# power.net
KiCad netlist of a schematic drawn in Altium Designer
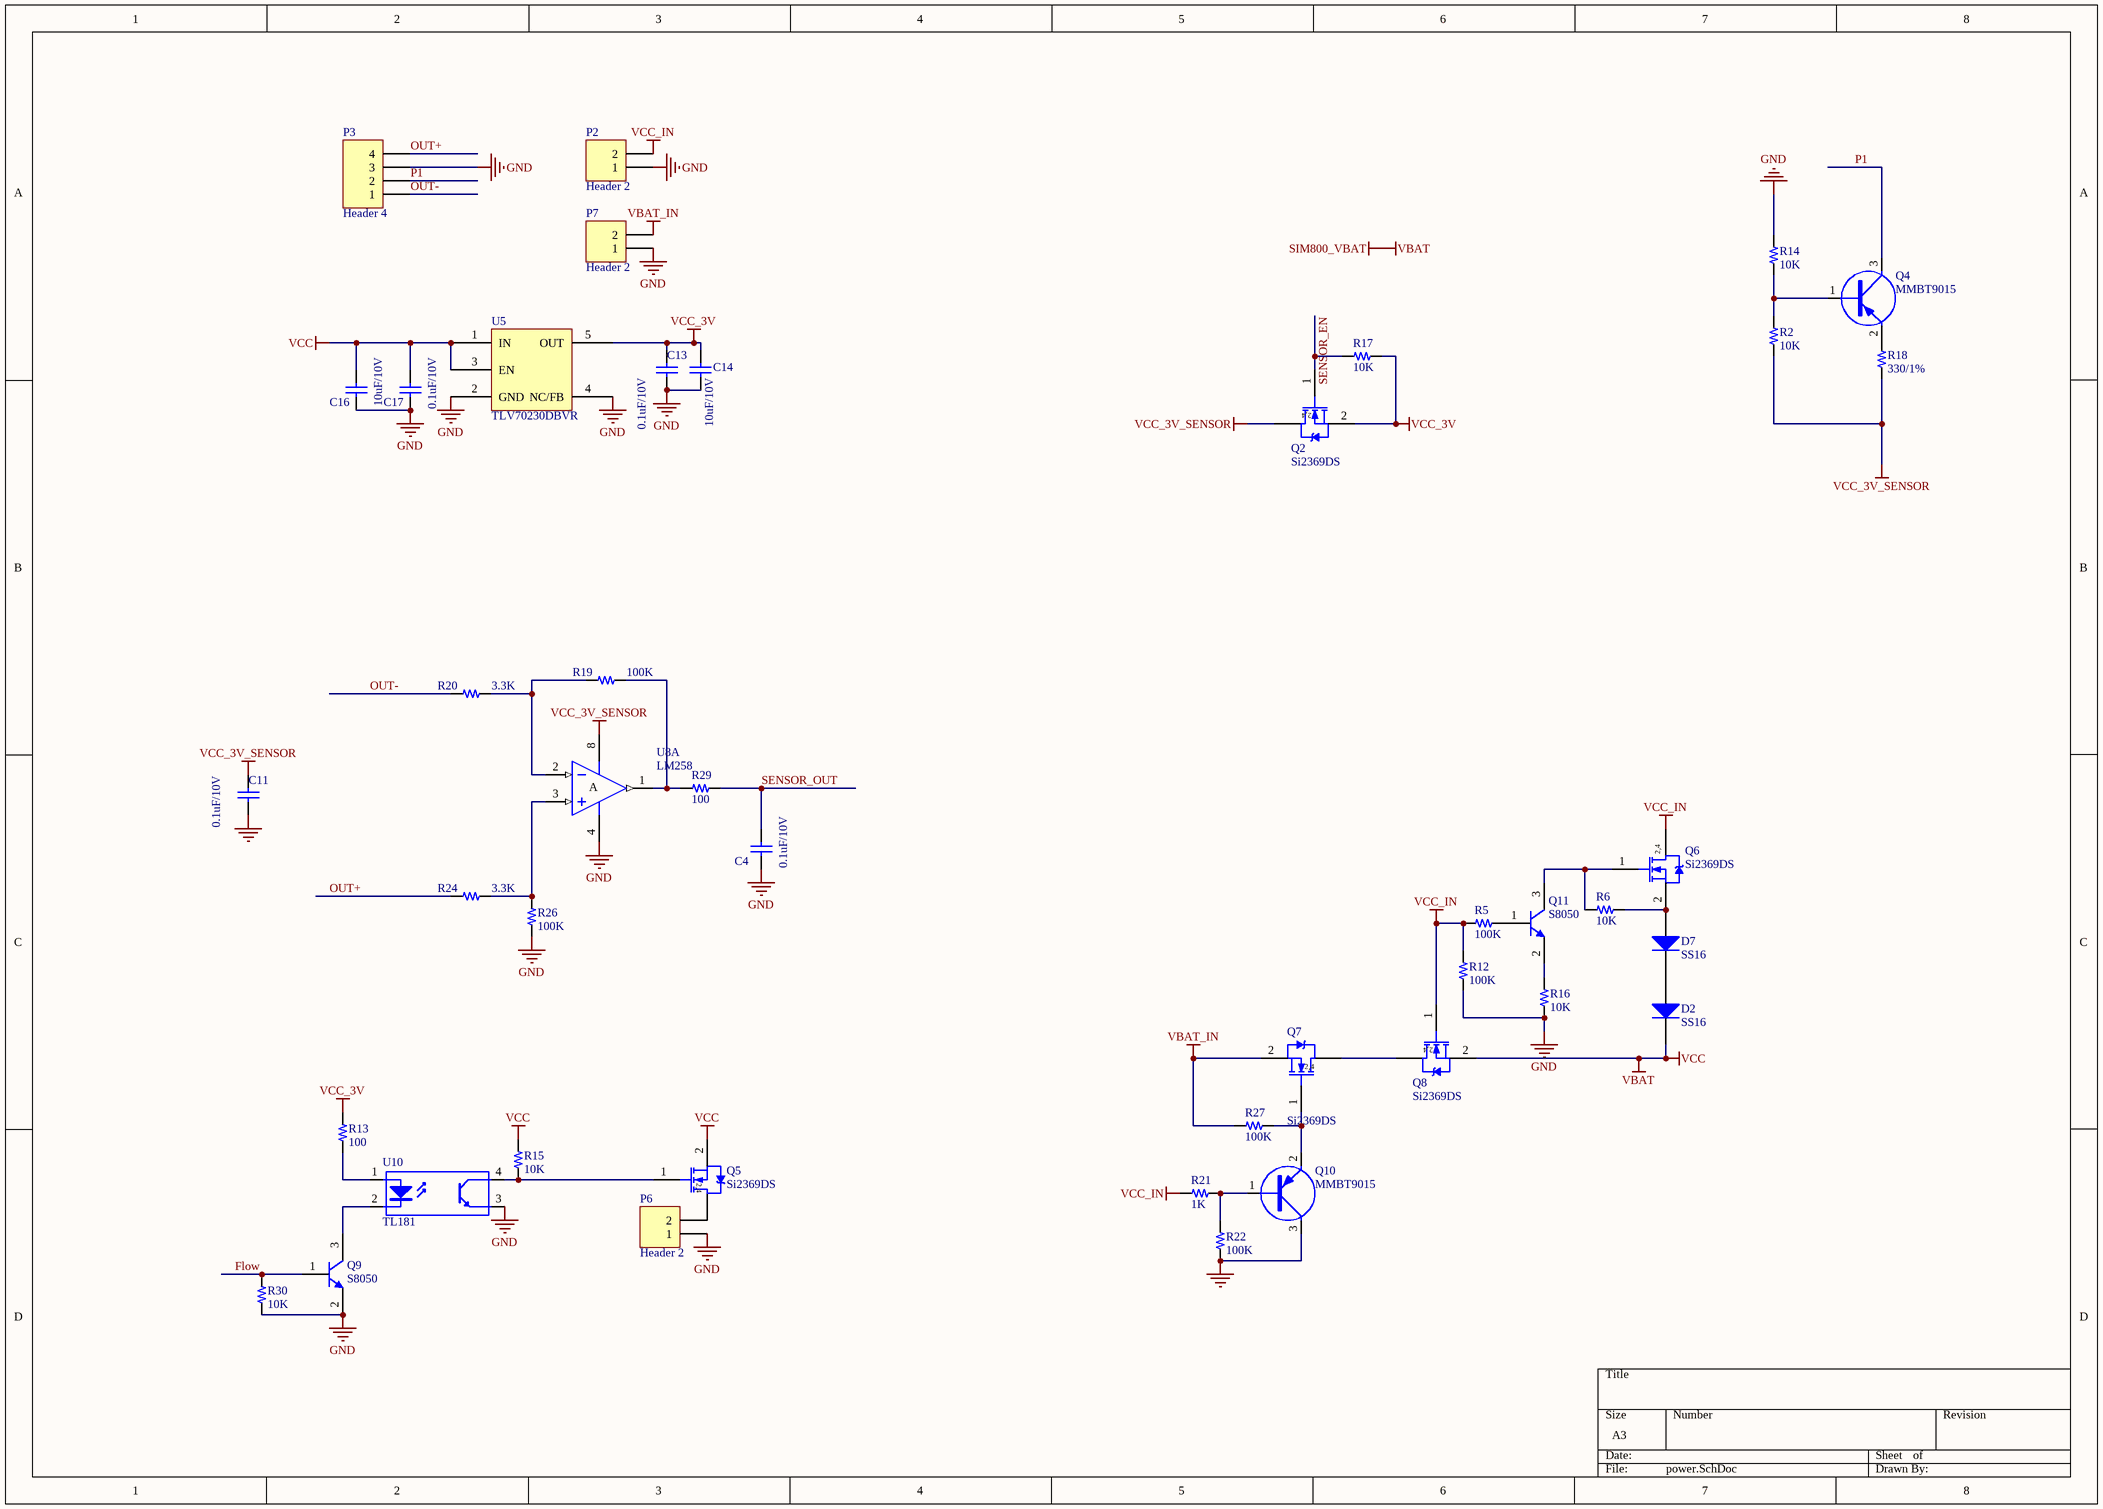
[diagram p0: power.SchDoc]

(export (version "E")
  (design (tool "Eeschema 10.0.6"))
  (components
    (comp (ref "C4")
      (value "0.1uF/10V")
      (footprint "0603C")
      (description "Capacitor")
      (fields (field (name "PUBLISHER") "Altium Limited"))
      (libsource (lib "Miscellaneous Devices") (part "Cap"))
    )
    (comp (ref "C11")
      (value "0.1uF/10V")
      (footprint "0603C")
      (description "Capacitor")
      (fields (field (name "PUBLISHER") "Altium Limited"))
      (libsource (lib "Miscellaneous Devices") (part "Cap"))
    )
    (comp (ref "C13")
      (value "0.1uF/10V")
      (footprint "0603C")
      (description "Capacitor")
      (fields (field (name "PUBLISHER") "Altium Limited"))
      (libsource (lib "Miscellaneous Devices") (part "Cap"))
    )
    (comp (ref "C14")
      (value "10uF/10V")
      (footprint "0603C")
      (description "Capacitor")
      (fields (field (name "PUBLISHER") "Altium Limited"))
      (libsource (lib "Miscellaneous Devices") (part "Cap"))
    )
    (comp (ref "C16")
      (value "10uF/10V")
      (footprint "0603C")
      (description "Capacitor")
      (fields (field (name "PUBLISHER") "Altium Limited"))
      (libsource (lib "Miscellaneous Devices") (part "Cap"))
    )
    (comp (ref "C17")
      (value "0.1uF/10V")
      (footprint "0603C")
      (description "Capacitor")
      (fields (field (name "PUBLISHER") "Altium Limited"))
      (libsource (lib "Miscellaneous Devices") (part "Cap"))
    )
    (comp (ref "D2")
      (value "SS16")
      (footprint "SMA")
      (description "High Conductance Fast Diode")
      (fields (field (name "PUBLISHER") "Altium Limited"))
      (libsource (lib "Miscellaneous Devices") (part "Diode 1N4148"))
    )
    (comp (ref "D7")
      (value "SS16")
      (footprint "SMA")
      (description "High Conductance Fast Diode")
      (fields (field (name "PUBLISHER") "Altium Limited"))
      (libsource (lib "Miscellaneous Devices") (part "Diode 1N4148"))
    )
    (comp (ref "P2")
      (value "Header 2")
      (footprint "2X2.54MM")
      (description "Header, 2-Pin")
      (fields (field (name "PUBLISHER") "Altium Limited"))
      (libsource (lib "Miscellaneous Connectors") (part "Header 2"))
    )
    (comp (ref "P3")
      (value "Header 4")
      (footprint "HDR1X4")
      (description "Header, 4-Pin")
      (fields (field (name "PUBLISHER") "Altium Limited"))
      (libsource (lib "Miscellaneous Connectors") (part "Header 4"))
    )
    (comp (ref "P6")
      (value "Header 2")
      (footprint "HDR1X2")
      (description "Header, 2-Pin")
      (fields (field (name "PUBLISHER") "Altium Limited"))
      (libsource (lib "Miscellaneous Connectors") (part "Header 2"))
    )
    (comp (ref "P7")
      (value "Header 2")
      (footprint "2X2.54MM")
      (description "Header, 2-Pin")
      (fields (field (name "PUBLISHER") "Altium Limited"))
      (libsource (lib "Miscellaneous Connectors") (part "Header 2"))
    )
    (comp (ref "Q2")
      (value "Si2369DS")
      (footprint "SOT23-3")
      (description "BUK92150-55A")
      (fields (field (name "PUBLISHER") "Altium Limited"))
      (libsource (lib "Schlib1") (part "BUK92150-55A"))
    )
    (comp (ref "Q4") (value "MMBT9015") (footprint "SOT23-3") (libsource (lib "Schlib1") (part "PNP")))
    (comp (ref "Q5")
      (value "Si2369DS")
      (footprint "SOT23-3")
      (description "BUK92150-55A")
      (fields (field (name "PUBLISHER") "Altium Limited"))
      (libsource (lib "") (part "BUK92150-55A_1"))
    )
    (comp (ref "Q6")
      (value "Si2369DS")
      (footprint "SOT23-3")
      (description "BUK92150-55A")
      (fields (field (name "PUBLISHER") "Altium Limited"))
      (libsource (lib "") (part "BUK92150-55A_1"))
    )
    (comp (ref "Q7")
      (value "Si2369DS")
      (footprint "SOT23-3")
      (description "BUK92150-55A")
      (fields (field (name "PUBLISHER") "Altium Limited"))
      (libsource (lib "Schlib1") (part "BUK92150-55A"))
    )
    (comp (ref "Q8")
      (value "Si2369DS")
      (footprint "SOT23-3")
      (description "BUK92150-55A")
      (fields (field (name "PUBLISHER") "Altium Limited"))
      (libsource (lib "Schlib1") (part "BUK92150-55A"))
    )
    (comp (ref "Q9") (value "S8050") (footprint "SOT23-3") (libsource (lib "Schlib1") (part "NPN")))
    (comp (ref "Q10") (value "MMBT9015") (footprint "SOT23-3") (libsource (lib "Schlib1") (part "PNP")))
    (comp (ref "Q11") (value "S8050") (footprint "SOT23-3") (libsource (lib "Schlib1") (part "NPN")))
    (comp (ref "R2") (value "10K") (footprint "0603R") (description "R") (libsource (lib "JRJ_1") (part "R")))
    (comp (ref "R5")
      (value "100K")
      (footprint "0603R")
      (description "R")
      (libsource (lib "JRJ_1") (part "R"))
    )
    (comp (ref "R6") (value "10K") (footprint "0603R") (description "R") (libsource (lib "JRJ_1") (part "R")))
    (comp (ref "R12")
      (value "100K")
      (footprint "0603R")
      (description "R")
      (libsource (lib "JRJ_1") (part "R"))
    )
    (comp (ref "R13")
      (value "100")
      (footprint "0603R")
      (description "R")
      (libsource (lib "JRJ_1") (part "R"))
    )
    (comp (ref "R14")
      (value "10K")
      (footprint "0603R")
      (description "R")
      (libsource (lib "JRJ_1") (part "R"))
    )
    (comp (ref "R15")
      (value "10K")
      (footprint "0603R")
      (description "R")
      (libsource (lib "JRJ_1") (part "R"))
    )
    (comp (ref "R16")
      (value "10K")
      (footprint "0603R")
      (description "R")
      (libsource (lib "JRJ_1") (part "R"))
    )
    (comp (ref "R17")
      (value "10K")
      (footprint "0603R")
      (description "R")
      (libsource (lib "JRJ_1") (part "R"))
    )
    (comp (ref "R18")
      (value "330/1%")
      (footprint "0603R")
      (description "R")
      (libsource (lib "JRJ_1") (part "R"))
    )
    (comp (ref "R19")
      (value "100K")
      (footprint "0603R")
      (description "R")
      (libsource (lib "JRJ_1") (part "R"))
    )
    (comp (ref "R20")
      (value "3.3K")
      (footprint "0603R")
      (description "R")
      (libsource (lib "JRJ_1") (part "R"))
    )
    (comp (ref "R21") (value "1K") (footprint "0603R") (description "R") (libsource (lib "JRJ_1") (part "R")))
    (comp (ref "R22")
      (value "100K")
      (footprint "0603R")
      (description "R")
      (libsource (lib "JRJ_1") (part "R"))
    )
    (comp (ref "R24")
      (value "3.3K")
      (footprint "0603R")
      (description "R")
      (libsource (lib "JRJ_1") (part "R"))
    )
    (comp (ref "R26")
      (value "100K")
      (footprint "0603R")
      (description "R")
      (libsource (lib "JRJ_1") (part "R"))
    )
    (comp (ref "R27")
      (value "100K")
      (footprint "0603R")
      (description "R")
      (libsource (lib "JRJ_1") (part "R"))
    )
    (comp (ref "R29")
      (value "100")
      (footprint "0603R")
      (description "R")
      (libsource (lib "JRJ_1") (part "R"))
    )
    (comp (ref "R30")
      (value "10K")
      (footprint "0603R")
      (description "R")
      (libsource (lib "JRJ_1") (part "R"))
    )
    (comp (ref "U5")
      (value "TLV70230DBVR")
      (footprint "SOT23-5(DBV)")
      (libsource (lib "Schlib_20110825") (part "TLV70230DBVR"))
    )
    (comp (ref "U8") (value "LM258") (footprint "so-8") (libsource (lib "Schlib_20110825") (part "LM258")))
    (comp (ref "U10")
      (value "TL181")
      (footprint "DIP-4")
      (description "4-Pin Phototransistor Optocoupler")
      (fields (field (name "PUBLISHER") "Altium Limited"))
      (libsource (lib "Miscellaneous Devices") (part "Optoisolator1"))
    )
  )
  (nets
    (net (code "1") (name "/Flow") (class "Default")
      (node (ref "Q9") (pin "1") (pinfunction "B_1") (pintype "passive"))
      (node (ref "R30") (pin "2") (pintype "passive"))
    )
    (net (code "2") (name "/OUT+") (class "Default")
      (node (ref "P3") (pin "4") (pinfunction "4_4") (pintype "passive"))
      (node (ref "R24") (pin "1") (pintype "passive"))
    )
    (net (code "3") (name "/OUT-") (class "Default")
      (node (ref "P3") (pin "1") (pinfunction "1_1") (pintype "passive"))
      (node (ref "R20") (pin "1") (pintype "passive"))
    )
    (net (code "4") (name "/P1") (class "Default")
      (node (ref "P3") (pin "2") (pinfunction "2_2") (pintype "passive"))
      (node (ref "Q4") (pin "3") (pinfunction "C_3") (pintype "passive"))
    )
    (net (code "5") (name "/SENSOR_EN") (class "Default")
      (node (ref "Q2") (pin "1") (pinfunction "G_1") (pintype "passive"))
      (node (ref "R17") (pin "2") (pintype "passive"))
    )
    (net (code "6") (name "/SENSOR_OUT") (class "Default")
      (node (ref "C4") (pin "1") (pinfunction "1_1") (pintype "passive"))
      (node (ref "R29") (pin "2") (pintype "passive"))
    )
    (net (code "7") (name "GND") (class "Default")
      (node (ref "C11") (pin "2") (pinfunction "2_2") (pintype "passive"))
      (node (ref "C13") (pin "2") (pinfunction "2_2") (pintype "passive"))
      (node (ref "C14") (pin "1") (pinfunction "1_1") (pintype "passive"))
      (node (ref "C16") (pin "1") (pinfunction "1_1") (pintype "passive"))
      (node (ref "C17") (pin "2") (pinfunction "2_2") (pintype "passive"))
      (node (ref "C4") (pin "2") (pinfunction "2_2") (pintype "passive"))
      (node (ref "P2") (pin "1") (pinfunction "1_1") (pintype "passive"))
      (node (ref "P3") (pin "3") (pinfunction "3_3") (pintype "passive"))
      (node (ref "P6") (pin "1") (pinfunction "1_1") (pintype "passive"))
      (node (ref "P7") (pin "1") (pinfunction "1_1") (pintype "passive"))
      (node (ref "Q10") (pin "3") (pinfunction "C_3") (pintype "passive"))
      (node (ref "Q9") (pin "2") (pinfunction "E_2") (pintype "passive"))
      (node (ref "R12") (pin "2") (pintype "passive"))
      (node (ref "R14") (pin "2") (pintype "passive"))
      (node (ref "R16") (pin "1") (pintype "passive"))
      (node (ref "R22") (pin "1") (pintype "passive"))
      (node (ref "R26") (pin "1") (pintype "passive"))
      (node (ref "R30") (pin "1") (pintype "passive"))
      (node (ref "U10") (pin "3") (pinfunction "E_3") (pintype "passive"))
      (node (ref "U5") (pin "2") (pinfunction "GND_2") (pintype "passive"))
      (node (ref "U5") (pin "4") (pinfunction "NC/FB_4") (pintype "passive"))
      (node (ref "U8") (pin "4") (pinfunction "V-_4") (pintype "power_in"))
    )
    (net (code "8") (name "Net-(D2-A)") (class "Default")
      (node (ref "D2") (pin "1") (pinfunction "A_1") (pintype "passive"))
      (node (ref "D7") (pin "2") (pinfunction "K_2") (pintype "passive"))
    )
    (net (code "9") (name "Net-(D7-A)") (class "Default")
      (node (ref "D7") (pin "1") (pinfunction "A_1") (pintype "passive"))
      (node (ref "Q6") (pin "2") (pinfunction "S_2") (pintype "passive"))
      (node (ref "R6") (pin "1") (pintype "passive"))
    )
    (net (code "10") (name "Net-(Q4-B)") (class "Default")
      (node (ref "Q4") (pin "1") (pinfunction "B_1") (pintype "passive"))
      (node (ref "R14") (pin "1") (pintype "passive"))
      (node (ref "R2") (pin "2") (pintype "passive"))
    )
    (net (code "11") (name "Net-(Q4-E)") (class "Default")
      (node (ref "Q4") (pin "2") (pinfunction "E_2") (pintype "passive"))
      (node (ref "R18") (pin "2") (pintype "passive"))
    )
    (net (code "12") (name "Net-(Q5-D)") (class "Default")
      (node (ref "P6") (pin "2") (pinfunction "2_2") (pintype "passive"))
      (node (ref "Q5") (pin "3") (pinfunction "D_3") (pintype "passive"))
    )
    (net (code "13") (name "Net-(Q5-G)") (class "Default")
      (node (ref "Q5") (pin "1") (pinfunction "G_1") (pintype "passive"))
      (node (ref "R15") (pin "1") (pintype "passive"))
      (node (ref "U10") (pin "4") (pinfunction "C_4") (pintype "passive"))
    )
    (net (code "14") (name "Net-(Q7-D)") (class "Default")
      (node (ref "Q7") (pin "3") (pinfunction "D_3") (pintype "passive"))
      (node (ref "Q8") (pin "3") (pinfunction "D_3") (pintype "passive"))
    )
    (net (code "15") (name "Net-(Q9-C)") (class "Default")
      (node (ref "Q9") (pin "3") (pinfunction "C_3") (pintype "passive"))
      (node (ref "U10") (pin "2") (pinfunction "K_2") (pintype "passive"))
    )
    (net (code "16") (name "Net-(Q10-B)") (class "Default")
      (node (ref "Q10") (pin "1") (pinfunction "B_1") (pintype "passive"))
      (node (ref "R21") (pin "2") (pintype "passive"))
      (node (ref "R22") (pin "2") (pintype "passive"))
    )
    (net (code "17") (name "Net-(Q10-E)") (class "Default")
      (node (ref "Q10") (pin "2") (pinfunction "E_2") (pintype "passive"))
      (node (ref "Q7") (pin "1") (pinfunction "G_1") (pintype "passive"))
      (node (ref "R27") (pin "2") (pintype "passive"))
    )
    (net (code "18") (name "Net-(Q11-B)") (class "Default")
      (node (ref "Q11") (pin "1") (pinfunction "B_1") (pintype "passive"))
      (node (ref "R5") (pin "2") (pintype "passive"))
    )
    (net (code "19") (name "Net-(Q11-C)") (class "Default")
      (node (ref "Q11") (pin "3") (pinfunction "C_3") (pintype "passive"))
      (node (ref "Q6") (pin "1") (pinfunction "G_1") (pintype "passive"))
      (node (ref "R6") (pin "2") (pintype "passive"))
    )
    (net (code "20") (name "Net-(Q11-E)") (class "Default")
      (node (ref "Q11") (pin "2") (pinfunction "E_2") (pintype "passive"))
      (node (ref "R16") (pin "2") (pintype "passive"))
    )
    (net (code "21") (name "Net-(U8A-IN+)") (class "Default")
      (node (ref "R24") (pin "2") (pintype "passive"))
      (node (ref "R26") (pin "2") (pintype "passive"))
      (node (ref "U8") (pin "3") (pinfunction "IN+_3") (pintype "input"))
    )
    (net (code "22") (name "Net-(U8A-IN-)") (class "Default")
      (node (ref "R19") (pin "1") (pintype "passive"))
      (node (ref "R20") (pin "2") (pintype "passive"))
      (node (ref "U8") (pin "2") (pinfunction "IN-_2") (pintype "input"))
    )
    (net (code "23") (name "Net-(U8A-OUT)") (class "Default")
      (node (ref "R19") (pin "2") (pintype "passive"))
      (node (ref "R29") (pin "1") (pintype "passive"))
      (node (ref "U8") (pin "1") (pinfunction "OUT_1") (pintype "output"))
    )
    (net (code "24") (name "Net-(U10-A)") (class "Default")
      (node (ref "R13") (pin "1") (pintype "passive"))
      (node (ref "U10") (pin "1") (pinfunction "A_1") (pintype "passive"))
    )
    (net (code "25") (name "SIM800_VBAT") (class "Default")
      (node (ref "C16") (pin "2") (pinfunction "2_2") (pintype "passive"))
      (node (ref "C17") (pin "1") (pinfunction "1_1") (pintype "passive"))
      (node (ref "D2") (pin "2") (pinfunction "K_2") (pintype "passive"))
      (node (ref "Q5") (pin "2") (pinfunction "S_2") (pintype "passive"))
      (node (ref "Q8") (pin "2") (pinfunction "S_2") (pintype "passive"))
      (node (ref "R15") (pin "2") (pintype "passive"))
      (node (ref "U5") (pin "1") (pinfunction "IN_1") (pintype "passive"))
      (node (ref "U5") (pin "3") (pinfunction "EN_3") (pintype "passive"))
    )
    (net (code "26") (name "VBAT_IN") (class "Default")
      (node (ref "P7") (pin "2") (pinfunction "2_2") (pintype "passive"))
      (node (ref "Q7") (pin "2") (pinfunction "S_2") (pintype "passive"))
      (node (ref "R27") (pin "1") (pintype "passive"))
    )
    (net (code "27") (name "VCC_3V") (class "Default")
      (node (ref "C13") (pin "1") (pinfunction "1_1") (pintype "passive"))
      (node (ref "C14") (pin "2") (pinfunction "2_2") (pintype "passive"))
      (node (ref "Q2") (pin "2") (pinfunction "S_2") (pintype "passive"))
      (node (ref "R13") (pin "2") (pintype "passive"))
      (node (ref "R17") (pin "1") (pintype "passive"))
      (node (ref "U5") (pin "5") (pinfunction "OUT_5") (pintype "passive"))
    )
    (net (code "28") (name "VCC_3V_SENSOR") (class "Default")
      (node (ref "C11") (pin "1") (pinfunction "1_1") (pintype "passive"))
      (node (ref "Q2") (pin "3") (pinfunction "D_3") (pintype "passive"))
      (node (ref "R18") (pin "1") (pintype "passive"))
      (node (ref "R2") (pin "1") (pintype "passive"))
      (node (ref "U8") (pin "8") (pinfunction "V+_8") (pintype "power_in"))
    )
    (net (code "29") (name "VCC_IN") (class "Default")
      (node (ref "P2") (pin "2") (pinfunction "2_2") (pintype "passive"))
      (node (ref "Q6") (pin "3") (pinfunction "D_3") (pintype "passive"))
      (node (ref "Q8") (pin "1") (pinfunction "G_1") (pintype "passive"))
      (node (ref "R12") (pin "1") (pintype "passive"))
      (node (ref "R21") (pin "1") (pintype "passive"))
      (node (ref "R5") (pin "1") (pintype "passive"))
    )
  )
)
